# POWER.net
KiCad netlist of a schematic drawn in Altium Designer
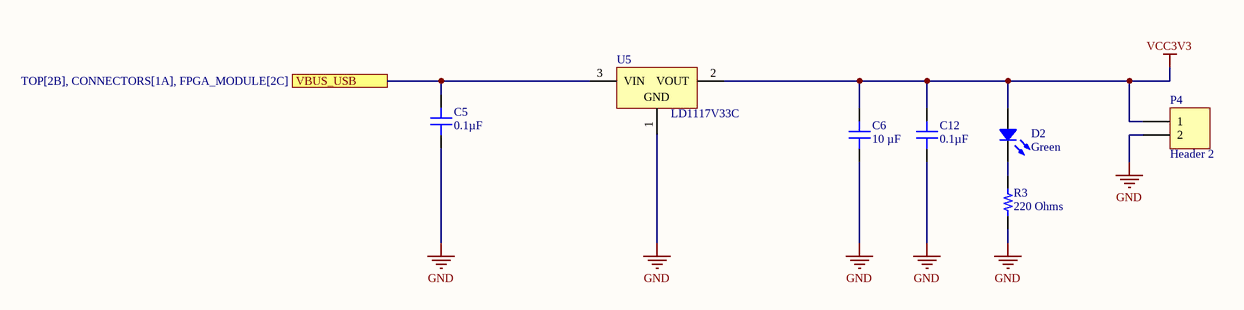
[diagram p0: POWER.SchDoc]

(export (version "E")
  (design (tool "Eeschema 10.0.6"))
  (components
    (comp (ref "C5")
      (value "0.1µF")
      (footprint "CAP 0402_1005")
      (description "CAP CER 0.1UF 10V X7R 0402")
      (fields (field (name "PART NUMBER") "0402ZC104KAT2A") (field (name "MANUFACTURER") "AVX Corporation"))
      (libsource (lib "Celestial") (part "Capacitor"))
    )
    (comp (ref "C6")
      (value "10 µF")
      (footprint "CAP 1206_3216 - 0.8MM")
      (description "CAP CER 10UF 16V X5R 1206")
      (fields (field (name "PART NUMBER") "EMK316BJ106MD-T") (field (name "MANUFACTURER") "Taiyo Yuden"))
      (libsource (lib "Celestial") (part "Capacitor"))
    )
    (comp (ref "C12")
      (value "0.1µF")
      (footprint "CAP 0402_1005")
      (description "CAP CER 0.1UF 10V X7R 0402")
      (fields (field (name "PART NUMBER") "0402ZC104KAT2A") (field (name "MANUFACTURER") "AVX Corporation"))
      (libsource (lib "Celestial") (part "Capacitor"))
    )
    (comp (ref "D2")
      (value "Green")
      (footprint "LED 1206_3216 GREEN")
      (description "LED SMD")
      (fields (field (name "PART NUMBER") "APTL3216ZGCK-01") (field (name "MANUFACTURER") "Kingbright"))
      (libsource (lib "Celestial") (part "LED"))
    )
    (comp (ref "P4")
      (value "Header 2")
      (footprint "HDR1X2")
      (description "Header, 2-Pin")
      (fields (field (name "PUBLISHER") "Altium Limited"))
      (libsource (lib "Miscellaneous Connectors") (part "Header 2"))
    )
    (comp (ref "R3")
      (value "220 Ohms")
      (footprint "RES 0402_1005")
      (description "RES 220 OHM 1% 1/8W 0402")
      (fields
        (field (name "PART NUMBER") "CRGP0402F220R")
        (field (name "MANUFACTURER") "TE Connectivity Passive Product")
      )
      (libsource (lib "Celestial") (part "Resistor"))
    )
    (comp (ref "U5")
      (value "LD1117V33C")
      (footprint "TO220")
      (description "Fixed Low Drop Positive Voltage Regulator, 3.3V, 3-Pin TO-220")
      (libsource (lib "Altium Content Vault") (part "PM-REG-LD1117V-SIL3"))
    )
  )
  (nets
    (net (code "1") (name "/VBUS_USB") (class "Default")
      (node (ref "C5") (pin "2") (pinfunction "2_2") (pintype "passive"))
      (node (ref "U5") (pin "3") (pinfunction "VIN_3") (pintype "power_in"))
    )
    (net (code "2") (name "GND") (class "Default")
      (node (ref "C12") (pin "1") (pinfunction "1_1") (pintype "passive"))
      (node (ref "C5") (pin "1") (pinfunction "1_1") (pintype "passive"))
      (node (ref "C6") (pin "1") (pinfunction "1_1") (pintype "passive"))
      (node (ref "P4") (pin "2") (pinfunction "2_2") (pintype "passive"))
      (node (ref "R3") (pin "1") (pinfunction "1_1") (pintype "passive"))
      (node (ref "U5") (pin "1") (pinfunction "GND_1") (pintype "power_in"))
    )
    (net (code "3") (name "Net-(D2-Pad2)") (class "Default")
      (node (ref "D2") (pin "2") (pinfunction "2_2") (pintype "passive"))
      (node (ref "R3") (pin "2") (pinfunction "2_2") (pintype "passive"))
    )
    (net (code "4") (name "VCC3V3") (class "Default")
      (node (ref "C12") (pin "2") (pinfunction "2_2") (pintype "passive"))
      (node (ref "C6") (pin "2") (pinfunction "2_2") (pintype "passive"))
      (node (ref "D2") (pin "1") (pinfunction "1_1") (pintype "passive"))
      (node (ref "P4") (pin "1") (pinfunction "1_1") (pintype "passive"))
      (node (ref "U5") (pin "2") (pinfunction "VOUT_2") (pintype "power_in"))
    )
  )
)
